# Sheet1.net
KiCad netlist of a schematic drawn in Altium Designer
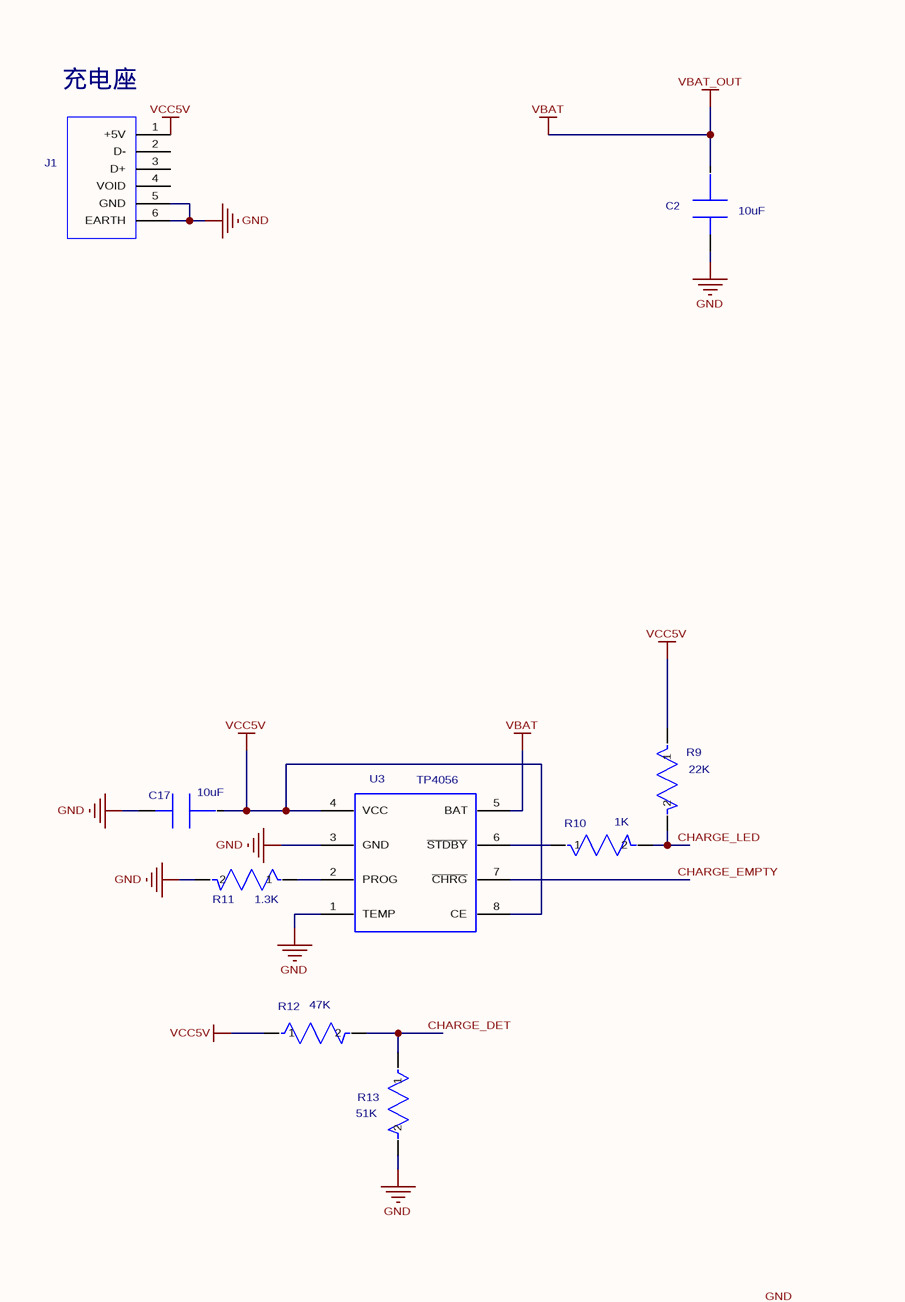
[diagram p0: Sheet1.SchDoc, top column 1 of 4]
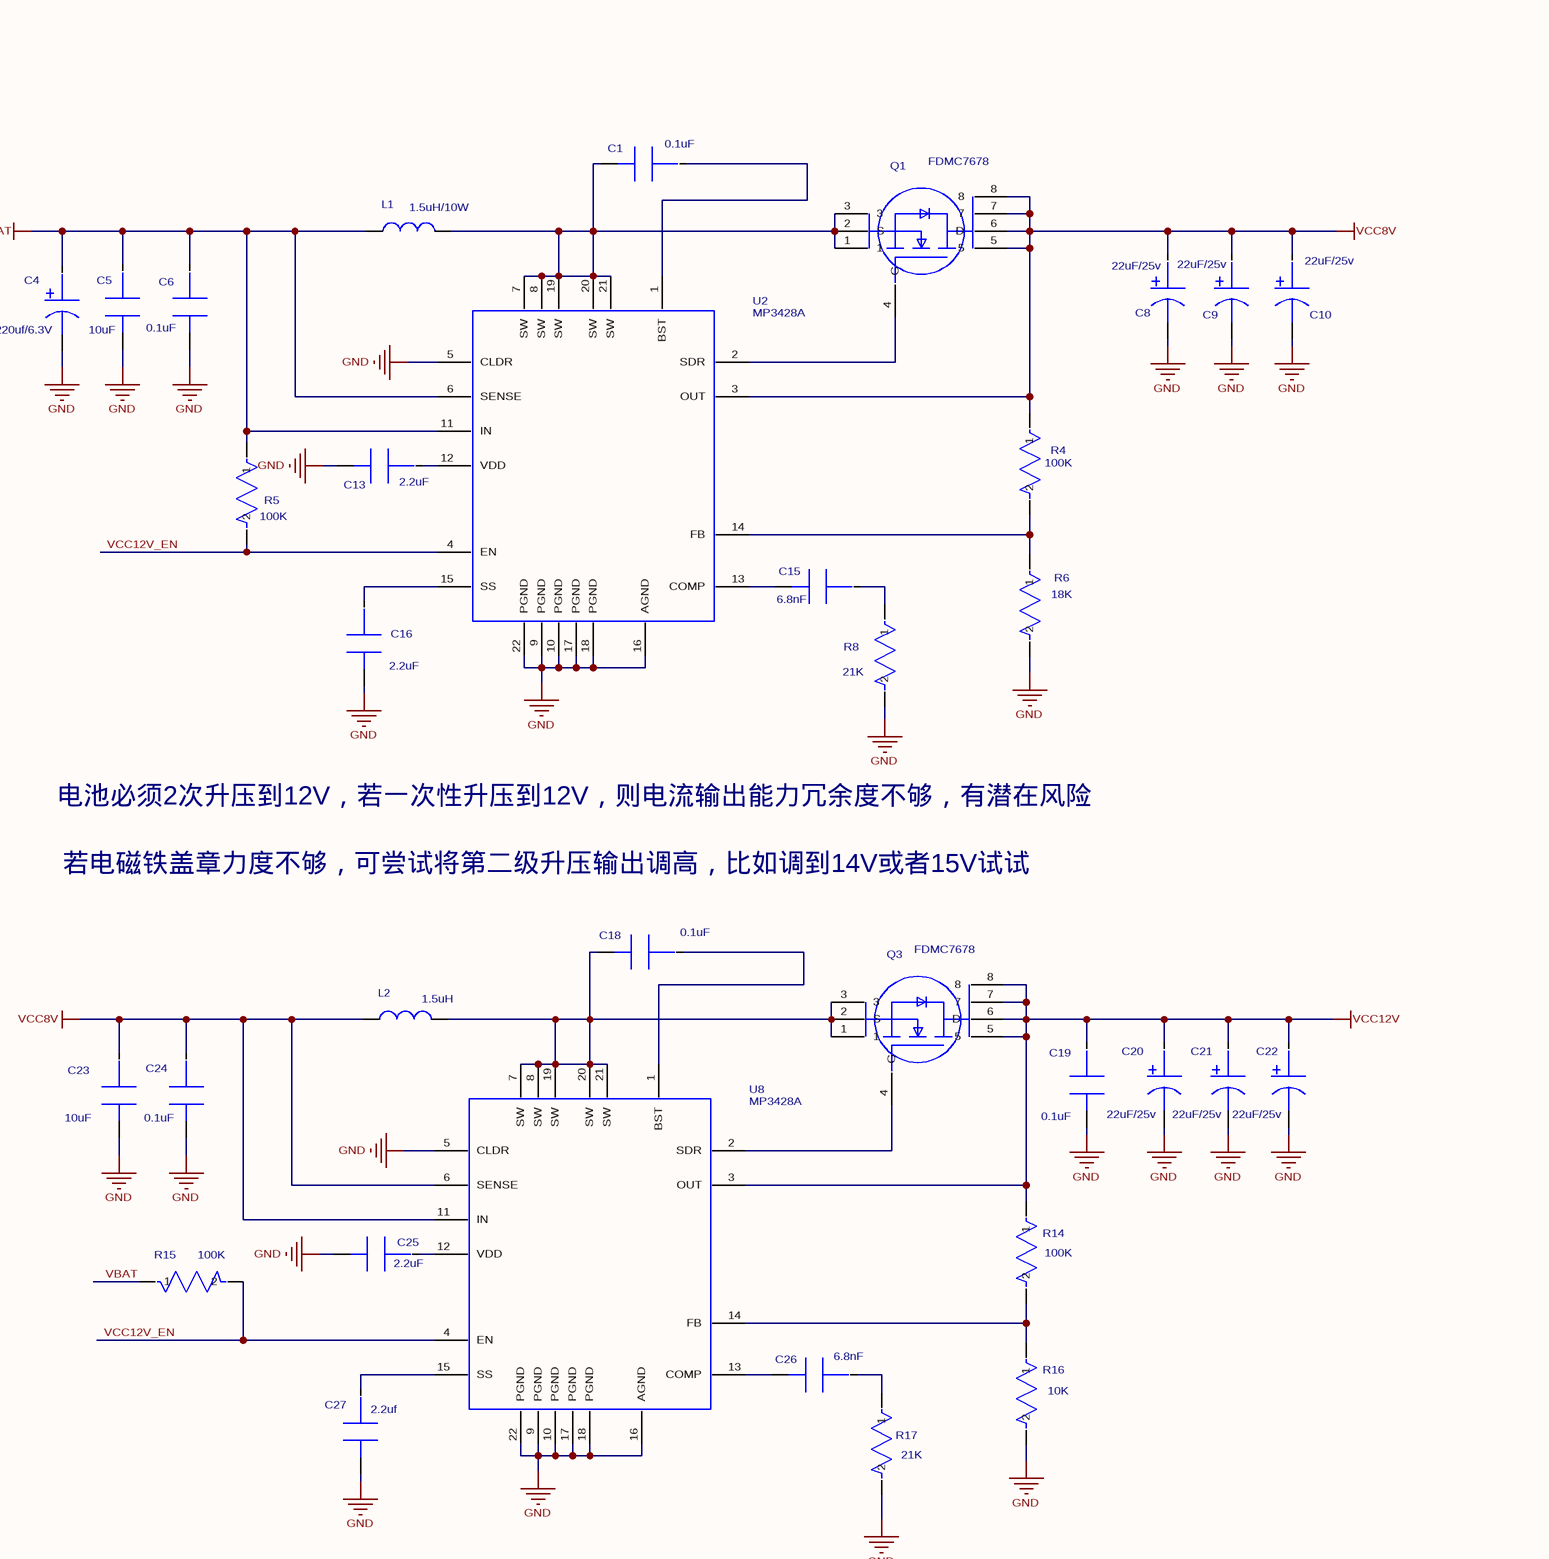
[diagram p1: Sheet1.SchDoc, top column 2 of 4]
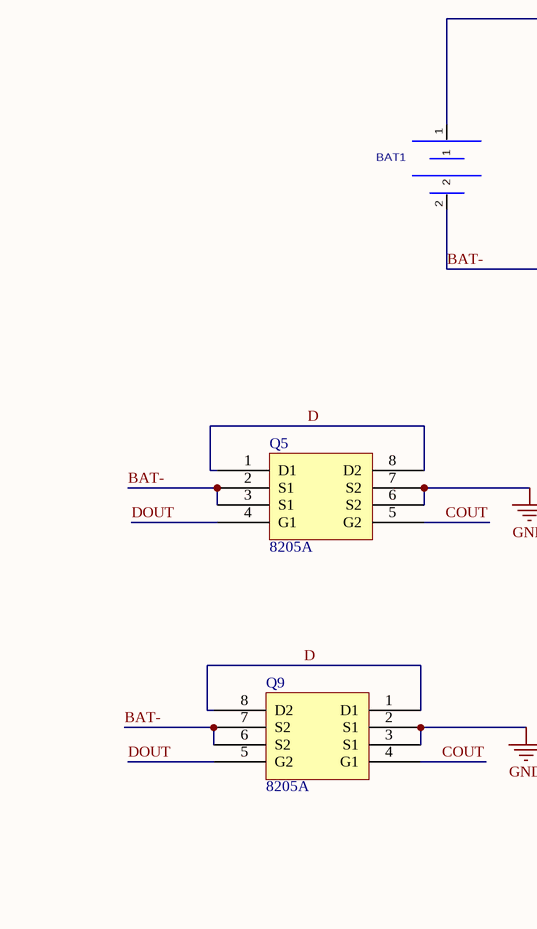
[diagram p2: Sheet1.SchDoc, top column 3 of 4]
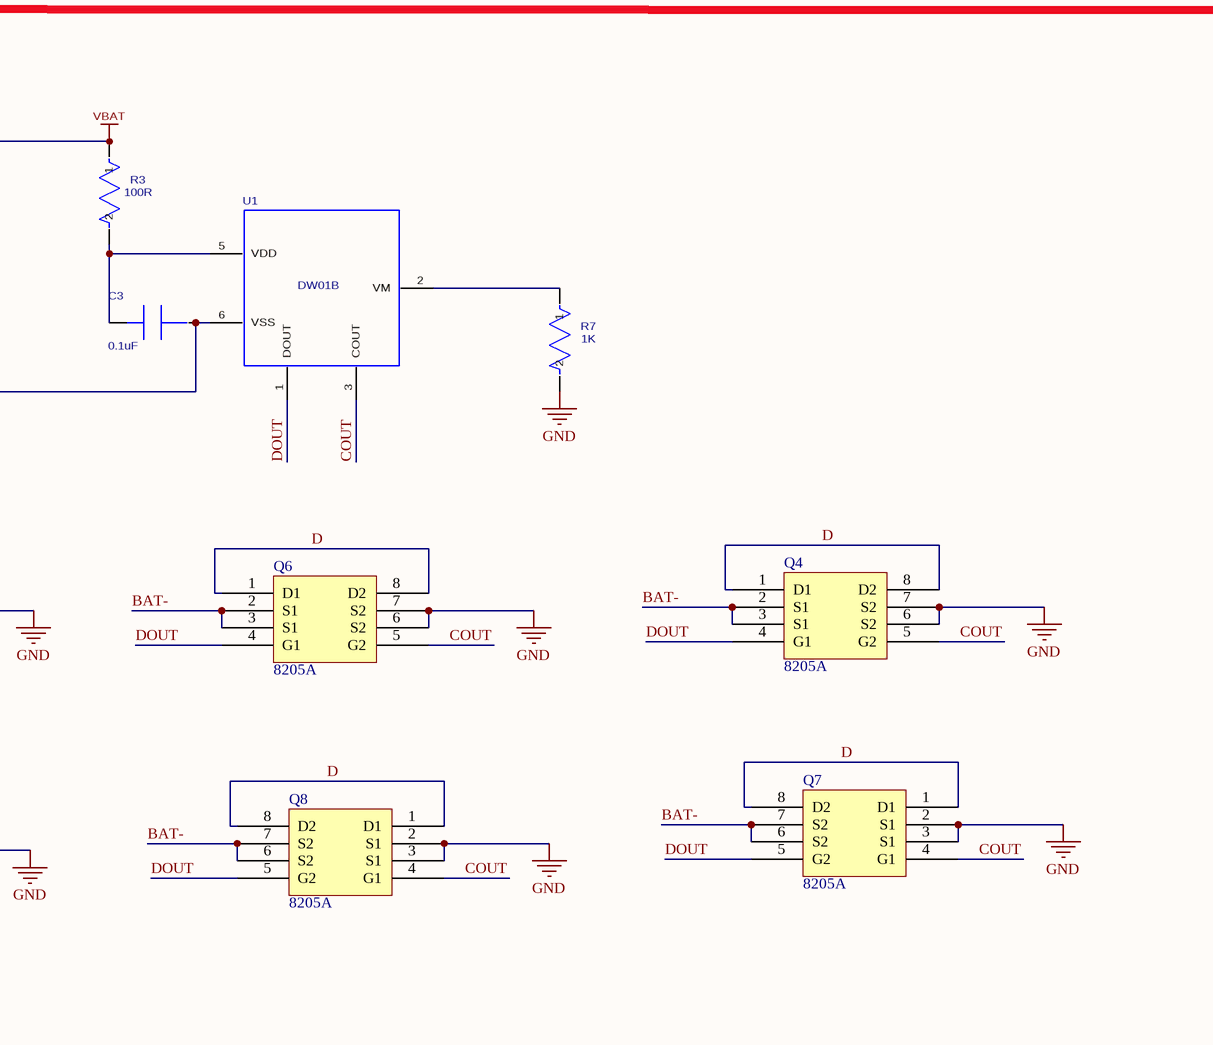
[diagram p3: Sheet1.SchDoc, top column 4 of 4]
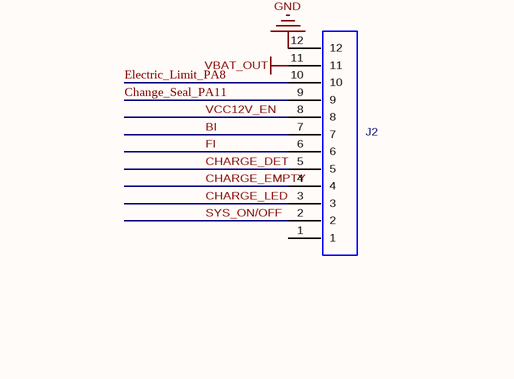
[diagram p4: Sheet1.SchDoc, bottom column 1 of 4]
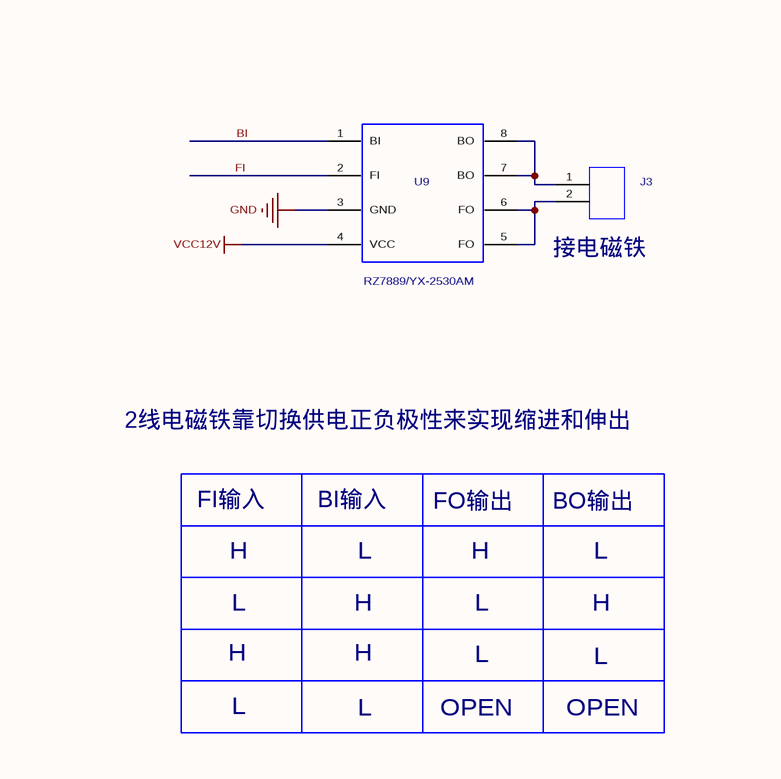
[diagram p5: Sheet1.SchDoc, bottom column 2 of 4]
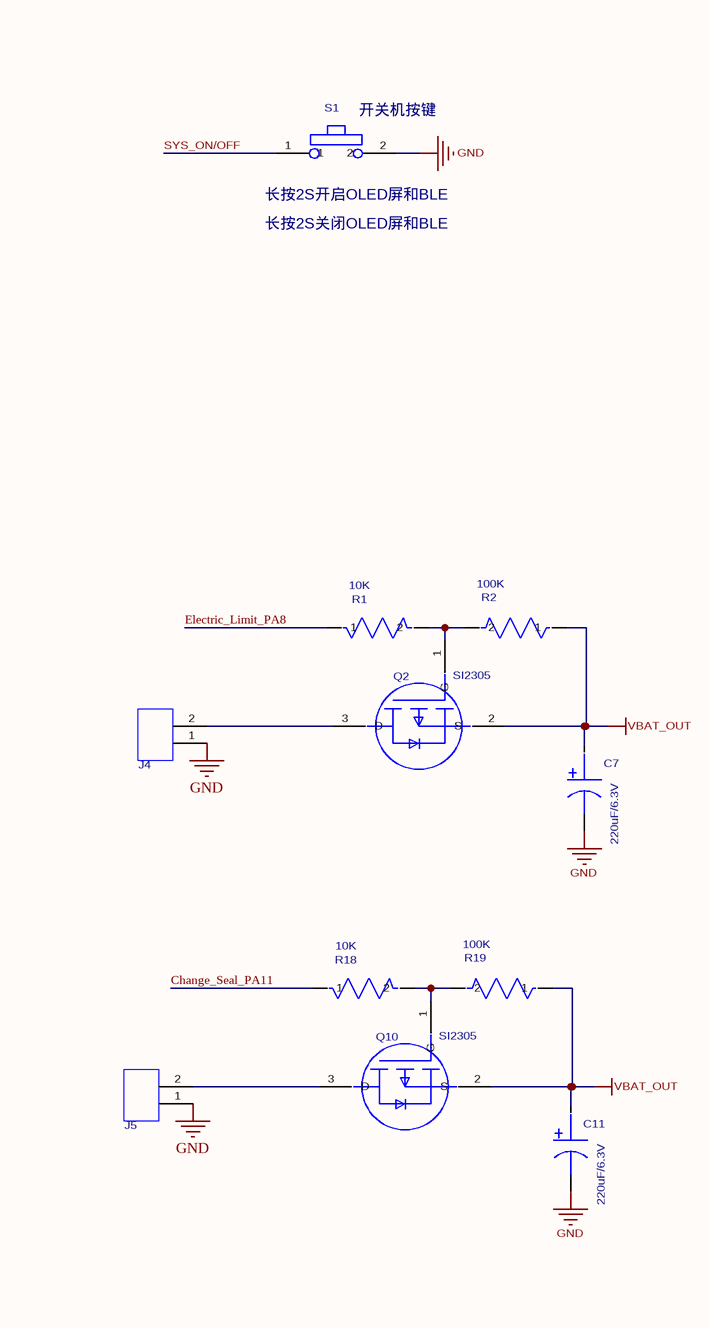
[diagram p6: Sheet1.SchDoc, bottom column 3 of 4]

(export (version "E")
  (design (tool "Eeschema 10.0.6"))
  (components
    (comp (ref "BAT1") (value "BAT1") (footprint "BAT18650_DIP2") (libsource (lib "*") (part "BAT1")))
    (comp (ref "C1") (value "0.1uF") (footprint "C0603") (libsource (lib "") (part "C_1")))
    (comp (ref "C2") (value "10uF") (footprint "C0603") (libsource (lib "") (part "C_1")))
    (comp (ref "C3") (value "0.1uF") (footprint "C0603") (libsource (lib "") (part "C_1")))
    (comp (ref "C4") (value "220uf/6.3V") (footprint "C1210-E") (libsource (lib "*") (part "C")))
    (comp (ref "C5") (value "10uF") (footprint "C0603") (libsource (lib "") (part "C_1")))
    (comp (ref "C6") (value "0.1uF") (footprint "C0603") (libsource (lib "") (part "C_1")))
    (comp (ref "C7") (value "220uF/6.3V") (footprint "C1210-E") (libsource (lib "*") (part "C")))
    (comp (ref "C8") (value "22uF/25v") (footprint "C1210-E") (libsource (lib "*") (part "C")))
    (comp (ref "C9") (value "22uF/25v") (footprint "C1210-E") (libsource (lib "*") (part "C")))
    (comp (ref "C10") (value "22uF/25v") (footprint "C1210-E") (libsource (lib "*") (part "C")))
    (comp (ref "C11") (value "220uF/6.3V") (footprint "C1210-E") (libsource (lib "*") (part "C")))
    (comp (ref "C13") (value "2.2uF") (footprint "C0603") (libsource (lib "") (part "C_1")))
    (comp (ref "C15") (value "6.8nF") (footprint "C0603") (libsource (lib "") (part "C_1")))
    (comp (ref "C16") (value "2.2uF") (footprint "C0603") (libsource (lib "") (part "C_1")))
    (comp (ref "C17") (value "10uF") (footprint "C0603") (libsource (lib "") (part "C_1")))
    (comp (ref "C18") (value "0.1uF") (footprint "C0603") (libsource (lib "") (part "C_1")))
    (comp (ref "C19") (value "0.1uF") (footprint "C0603") (libsource (lib "") (part "C_1")))
    (comp (ref "C20") (value "22uF/25v") (footprint "C1210-E") (libsource (lib "*") (part "C")))
    (comp (ref "C21") (value "22uF/25v") (footprint "C1210-E") (libsource (lib "*") (part "C")))
    (comp (ref "C22") (value "22uF/25v") (footprint "CAP12R5X30") (libsource (lib "*") (part "C")))
    (comp (ref "C23") (value "10uF") (footprint "C0603") (libsource (lib "") (part "C_1")))
    (comp (ref "C24") (value "0.1uF") (footprint "C0603") (libsource (lib "") (part "C_1")))
    (comp (ref "C25") (value "2.2uF") (footprint "C0603") (libsource (lib "") (part "C_1")))
    (comp (ref "C26") (value "6.8nF") (footprint "C0603") (libsource (lib "") (part "C_1")))
    (comp (ref "C27") (value "2.2uf") (footprint "C0603") (libsource (lib "") (part "C_1")))
    (comp (ref "J1") (value "HEADER_6_2") (footprint "MICRO_USB_J") (libsource (lib "*") (part "HEADER_6_2")))
    (comp (ref "J2") (value "CON12") (footprint "CON_12WT") (libsource (lib "*") (part "CON12")))
    (comp (ref "J3") (value "CON2") (footprint "CON1X2-2LOCK") (libsource (lib "*") (part "CON2")))
    (comp (ref "J4") (value "CON2") (footprint "CON1X2-2LOCK") (libsource (lib "*") (part "CON2")))
    (comp (ref "J5") (value "CON2") (footprint "CON1X2-2LOCK") (libsource (lib "*") (part "CON2")))
    (comp (ref "L1") (value "1.5uH/10W") (footprint "L0630") (libsource (lib "*") (part "L")))
    (comp (ref "L2") (value "1.5uH") (footprint "L0630") (libsource (lib "*") (part "L")))
    (comp (ref "Q1") (value "FDMC7678") (footprint "FDMC7678") (libsource (lib "*") (part "FDMC7678")))
    (comp (ref "Q2") (value "SI2305") (footprint "SOT23") (libsource (lib "*") (part "FDN338P")))
    (comp (ref "Q3") (value "FDMC7678") (footprint "FDMC7678") (libsource (lib "*") (part "FDMC7678")))
    (comp (ref "Q4") (value "8205A") (footprint "TSSOP8") (libsource (lib "") (part "8205A-TSSOP8_1")))
    (comp (ref "Q5") (value "8205A") (footprint "TSSOP8") (libsource (lib "") (part "8205A-TSSOP8_1")))
    (comp (ref "Q6") (value "8205A") (footprint "TSSOP8") (libsource (lib "") (part "8205A-TSSOP8_1")))
    (comp (ref "Q7")
      (value "8205A")
      (footprint "TSSOP8")
      (libsource (lib "PCB_Project") (part "8205A-TSSOP8"))
    )
    (comp (ref "Q8")
      (value "8205A")
      (footprint "TSSOP8")
      (libsource (lib "PCB_Project") (part "8205A-TSSOP8"))
    )
    (comp (ref "Q9")
      (value "8205A")
      (footprint "TSSOP8")
      (libsource (lib "PCB_Project") (part "8205A-TSSOP8"))
    )
    (comp (ref "Q10") (value "SI2305") (footprint "SOT23") (libsource (lib "*") (part "FDN338P")))
    (comp (ref "R1") (value "10K") (footprint "R0603") (libsource (lib "*") (part "R")))
    (comp (ref "R2") (value "100K") (footprint "R0603") (libsource (lib "*") (part "R")))
    (comp (ref "R3") (value "100R") (footprint "R0603") (libsource (lib "*") (part "R")))
    (comp (ref "R4") (value "100K") (footprint "R0603") (libsource (lib "*") (part "R")))
    (comp (ref "R5") (value "100K") (footprint "R0603") (libsource (lib "*") (part "R")))
    (comp (ref "R6") (value "18K") (footprint "R0603") (libsource (lib "*") (part "R")))
    (comp (ref "R7") (value "1K") (footprint "R0603") (libsource (lib "*") (part "R")))
    (comp (ref "R8") (value "21K") (footprint "R0603") (libsource (lib "*") (part "R")))
    (comp (ref "R9") (value "22K") (footprint "R0603") (libsource (lib "*") (part "R")))
    (comp (ref "R10") (value "1K") (footprint "R0603") (libsource (lib "*") (part "R")))
    (comp (ref "R11") (value "1.3K") (footprint "R0603") (libsource (lib "*") (part "R")))
    (comp (ref "R12") (value "47K") (footprint "R0603") (libsource (lib "*") (part "R")))
    (comp (ref "R13") (value "51K") (footprint "R0603") (libsource (lib "*") (part "R")))
    (comp (ref "R14") (value "100K") (footprint "R0603") (libsource (lib "*") (part "R")))
    (comp (ref "R15") (value "100K") (footprint "R0603") (libsource (lib "*") (part "R")))
    (comp (ref "R16") (value "10K") (footprint "R0603") (libsource (lib "*") (part "R")))
    (comp (ref "R17") (value "21K") (footprint "R0603") (libsource (lib "*") (part "R")))
    (comp (ref "R18") (value "10K") (footprint "R0603") (libsource (lib "*") (part "R")))
    (comp (ref "R19") (value "100K") (footprint "R0603") (libsource (lib "*") (part "R")))
    (comp (ref "S1") (value "SW_3X6X5") (footprint "SW3X6X3R5") (libsource (lib "*") (part "SW_3X6X5")))
    (comp (ref "U1") (value "DW01B") (footprint "SOT23-6") (libsource (lib "PCB_Project") (part "DW01V")))
    (comp (ref "U2") (value "MP3428A") (footprint "QFN22") (libsource (lib "PCB_Project") (part "MP3428A")))
    (comp (ref "U3") (value "TP4056") (footprint "SOIC8E") (libsource (lib "*") (part "TP4056")))
    (comp (ref "U8") (value "MP3428A") (footprint "QFN22") (libsource (lib "PCB_Project") (part "MP3428A")))
    (comp (ref "U9")
      (value "RZ7889/YX-2530AM")
      (footprint "SO8-5R2-1R27")
      (libsource (lib "*") (part "RZ7889/YX-2530AM"))
    )
  )
  (nets
    (net (code "1") (name "/BAT-") (class "Default")
      (node (ref "BAT1") (pin "2") (pinfunction "2_2") (pintype "passive"))
      (node (ref "C3") (pin "1") (pinfunction "1_1") (pintype "passive"))
      (node (ref "Q4") (pin "2") (pinfunction "S1_2") (pintype "passive"))
      (node (ref "Q4") (pin "3") (pinfunction "S1_3") (pintype "passive"))
      (node (ref "Q5") (pin "2") (pinfunction "S1_2") (pintype "passive"))
      (node (ref "Q5") (pin "3") (pinfunction "S1_3") (pintype "passive"))
      (node (ref "Q6") (pin "2") (pinfunction "S1_2") (pintype "passive"))
      (node (ref "Q6") (pin "3") (pinfunction "S1_3") (pintype "passive"))
      (node (ref "Q7") (pin "6") (pinfunction "S2_6") (pintype "passive"))
      (node (ref "Q7") (pin "7") (pinfunction "S2_7") (pintype "passive"))
      (node (ref "Q8") (pin "6") (pinfunction "S2_6") (pintype "passive"))
      (node (ref "Q8") (pin "7") (pinfunction "S2_7") (pintype "passive"))
      (node (ref "Q9") (pin "6") (pinfunction "S2_6") (pintype "passive"))
      (node (ref "Q9") (pin "7") (pinfunction "S2_7") (pintype "passive"))
      (node (ref "U1") (pin "6") (pinfunction "VSS_6") (pintype "passive"))
    )
    (net (code "2") (name "/BI") (class "Default")
      (node (ref "J2") (pin "7") (pinfunction "7_7") (pintype "passive"))
      (node (ref "U9") (pin "1") (pinfunction "BI_1") (pintype "passive"))
    )
    (net (code "3") (name "/CHARGE_DET") (class "Default")
      (node (ref "J2") (pin "5") (pinfunction "5_5") (pintype "passive"))
      (node (ref "R12") (pin "2") (pinfunction "2_2") (pintype "passive"))
      (node (ref "R13") (pin "1") (pinfunction "1_1") (pintype "passive"))
    )
    (net (code "4") (name "/CHARGE_EMPTY") (class "Default")
      (node (ref "J2") (pin "4") (pinfunction "4_4") (pintype "passive"))
      (node (ref "U3") (pin "7") (pinfunction "CHRG_7") (pintype "passive"))
    )
    (net (code "5") (name "/CHARGE_LED") (class "Default")
      (node (ref "J2") (pin "3") (pinfunction "3_3") (pintype "passive"))
      (node (ref "R10") (pin "2") (pinfunction "2_2") (pintype "passive"))
      (node (ref "R9") (pin "2") (pinfunction "2_2") (pintype "passive"))
    )
    (net (code "6") (name "/COUT") (class "Default")
      (node (ref "Q4") (pin "5") (pinfunction "G2_5") (pintype "passive"))
      (node (ref "Q5") (pin "5") (pinfunction "G2_5") (pintype "passive"))
      (node (ref "Q6") (pin "5") (pinfunction "G2_5") (pintype "passive"))
      (node (ref "Q7") (pin "4") (pinfunction "G1_4") (pintype "passive"))
      (node (ref "Q8") (pin "4") (pinfunction "G1_4") (pintype "passive"))
      (node (ref "Q9") (pin "4") (pinfunction "G1_4") (pintype "passive"))
      (node (ref "U1") (pin "3") (pinfunction "COUT_3") (pintype "passive"))
    )
    (net (code "7") (name "/Change_Seal_PA11") (class "Default")
      (node (ref "J2") (pin "9") (pinfunction "9_9") (pintype "passive"))
      (node (ref "R18") (pin "1") (pinfunction "1_1") (pintype "passive"))
    )
    (net (code "8") (name "/D") (class "Default")
      (node (ref "Q4") (pin "1") (pinfunction "D1_1") (pintype "passive"))
      (node (ref "Q4") (pin "8") (pinfunction "D2_8") (pintype "passive"))
      (node (ref "Q5") (pin "1") (pinfunction "D1_1") (pintype "passive"))
      (node (ref "Q5") (pin "8") (pinfunction "D2_8") (pintype "passive"))
      (node (ref "Q6") (pin "1") (pinfunction "D1_1") (pintype "passive"))
      (node (ref "Q6") (pin "8") (pinfunction "D2_8") (pintype "passive"))
      (node (ref "Q7") (pin "1") (pinfunction "D1_1") (pintype "passive"))
      (node (ref "Q7") (pin "8") (pinfunction "D2_8") (pintype "passive"))
      (node (ref "Q8") (pin "1") (pinfunction "D1_1") (pintype "passive"))
      (node (ref "Q8") (pin "8") (pinfunction "D2_8") (pintype "passive"))
      (node (ref "Q9") (pin "1") (pinfunction "D1_1") (pintype "passive"))
      (node (ref "Q9") (pin "8") (pinfunction "D2_8") (pintype "passive"))
    )
    (net (code "9") (name "/DOUT") (class "Default")
      (node (ref "Q4") (pin "4") (pinfunction "G1_4") (pintype "passive"))
      (node (ref "Q5") (pin "4") (pinfunction "G1_4") (pintype "passive"))
      (node (ref "Q6") (pin "4") (pinfunction "G1_4") (pintype "passive"))
      (node (ref "Q7") (pin "5") (pinfunction "G2_5") (pintype "passive"))
      (node (ref "Q8") (pin "5") (pinfunction "G2_5") (pintype "passive"))
      (node (ref "Q9") (pin "5") (pinfunction "G2_5") (pintype "passive"))
      (node (ref "U1") (pin "1") (pinfunction "DOUT_1") (pintype "passive"))
    )
    (net (code "10") (name "/Electric_Limit_PA8") (class "Default")
      (node (ref "J2") (pin "10") (pinfunction "10_10") (pintype "passive"))
      (node (ref "R1") (pin "1") (pinfunction "1_1") (pintype "passive"))
    )
    (net (code "11") (name "/FI") (class "Default")
      (node (ref "J2") (pin "6") (pinfunction "6_6") (pintype "passive"))
      (node (ref "U9") (pin "2") (pinfunction "FI_2") (pintype "passive"))
    )
    (net (code "12") (name "/SYS_ON{slash}OFF") (class "Default")
      (node (ref "J2") (pin "2") (pinfunction "2_2") (pintype "passive"))
      (node (ref "S1") (pin "1") (pinfunction "1_1") (pintype "passive"))
    )
    (net (code "13") (name "/VCC12V_EN") (class "Default")
      (node (ref "J2") (pin "8") (pinfunction "8_8") (pintype "passive"))
      (node (ref "R15") (pin "2") (pinfunction "2_2") (pintype "passive"))
      (node (ref "R5") (pin "2") (pinfunction "2_2") (pintype "passive"))
      (node (ref "U2") (pin "4") (pinfunction "EN_4") (pintype "passive"))
      (node (ref "U8") (pin "4") (pinfunction "EN_4") (pintype "passive"))
    )
    (net (code "14") (name "GND") (class "Default")
      (node (ref "C10") (pin "2") (pinfunction "2_2") (pintype "passive"))
      (node (ref "C11") (pin "2") (pinfunction "2_2") (pintype "passive"))
      (node (ref "C13") (pin "2") (pinfunction "2_2") (pintype "passive"))
      (node (ref "C16") (pin "2") (pinfunction "2_2") (pintype "passive"))
      (node (ref "C17") (pin "2") (pinfunction "2_2") (pintype "passive"))
      (node (ref "C19") (pin "2") (pinfunction "2_2") (pintype "passive"))
      (node (ref "C2") (pin "2") (pinfunction "2_2") (pintype "passive"))
      (node (ref "C20") (pin "2") (pinfunction "2_2") (pintype "passive"))
      (node (ref "C21") (pin "2") (pinfunction "2_2") (pintype "passive"))
      (node (ref "C22") (pin "2") (pinfunction "2_2") (pintype "passive"))
      (node (ref "C23") (pin "2") (pinfunction "2_2") (pintype "passive"))
      (node (ref "C24") (pin "2") (pinfunction "2_2") (pintype "passive"))
      (node (ref "C25") (pin "2") (pinfunction "2_2") (pintype "passive"))
      (node (ref "C27") (pin "2") (pinfunction "2_2") (pintype "passive"))
      (node (ref "C4") (pin "2") (pinfunction "2_2") (pintype "passive"))
      (node (ref "C5") (pin "2") (pinfunction "2_2") (pintype "passive"))
      (node (ref "C6") (pin "2") (pinfunction "2_2") (pintype "passive"))
      (node (ref "C7") (pin "2") (pinfunction "2_2") (pintype "passive"))
      (node (ref "C8") (pin "2") (pinfunction "2_2") (pintype "passive"))
      (node (ref "C9") (pin "2") (pinfunction "2_2") (pintype "passive"))
      (node (ref "J1") (pin "5") (pinfunction "GND_5") (pintype "passive"))
      (node (ref "J1") (pin "6") (pinfunction "EARTH_6") (pintype "passive"))
      (node (ref "J2") (pin "12") (pinfunction "12_12") (pintype "passive"))
      (node (ref "J4") (pin "1") (pinfunction "1_1") (pintype "passive"))
      (node (ref "J5") (pin "1") (pinfunction "1_1") (pintype "passive"))
      (node (ref "Q4") (pin "6") (pinfunction "S2_6") (pintype "passive"))
      (node (ref "Q4") (pin "7") (pinfunction "S2_7") (pintype "passive"))
      (node (ref "Q5") (pin "6") (pinfunction "S2_6") (pintype "passive"))
      (node (ref "Q5") (pin "7") (pinfunction "S2_7") (pintype "passive"))
      (node (ref "Q6") (pin "6") (pinfunction "S2_6") (pintype "passive"))
      (node (ref "Q6") (pin "7") (pinfunction "S2_7") (pintype "passive"))
      (node (ref "Q7") (pin "2") (pinfunction "S1_2") (pintype "passive"))
      (node (ref "Q7") (pin "3") (pinfunction "S1_3") (pintype "passive"))
      (node (ref "Q8") (pin "2") (pinfunction "S1_2") (pintype "passive"))
      (node (ref "Q8") (pin "3") (pinfunction "S1_3") (pintype "passive"))
      (node (ref "Q9") (pin "2") (pinfunction "S1_2") (pintype "passive"))
      (node (ref "Q9") (pin "3") (pinfunction "S1_3") (pintype "passive"))
      (node (ref "R11") (pin "2") (pinfunction "2_2") (pintype "passive"))
      (node (ref "R13") (pin "2") (pinfunction "2_2") (pintype "passive"))
      (node (ref "R16") (pin "2") (pinfunction "2_2") (pintype "passive"))
      (node (ref "R17") (pin "2") (pinfunction "2_2") (pintype "passive"))
      (node (ref "R6") (pin "2") (pinfunction "2_2") (pintype "passive"))
      (node (ref "R7") (pin "2") (pinfunction "2_2") (pintype "passive"))
      (node (ref "R8") (pin "2") (pinfunction "2_2") (pintype "passive"))
      (node (ref "S1") (pin "2") (pinfunction "2_2") (pintype "passive"))
      (node (ref "U2") (pin "10") (pinfunction "PGND_10") (pintype "passive"))
      (node (ref "U2") (pin "16") (pinfunction "AGND_16") (pintype "passive"))
      (node (ref "U2") (pin "17") (pinfunction "PGND_17") (pintype "passive"))
      (node (ref "U2") (pin "18") (pinfunction "PGND_18") (pintype "passive"))
      (node (ref "U2") (pin "22") (pinfunction "PGND_22") (pintype "passive"))
      (node (ref "U2") (pin "5") (pinfunction "CLDR_5") (pintype "passive"))
      (node (ref "U2") (pin "9") (pinfunction "PGND_9") (pintype "passive"))
      (node (ref "U3") (pin "1") (pinfunction "TEMP_1") (pintype "passive"))
      (node (ref "U3") (pin "3") (pinfunction "GND_3") (pintype "passive"))
      (node (ref "U8") (pin "10") (pinfunction "PGND_10") (pintype "passive"))
      (node (ref "U8") (pin "16") (pinfunction "AGND_16") (pintype "passive"))
      (node (ref "U8") (pin "17") (pinfunction "PGND_17") (pintype "passive"))
      (node (ref "U8") (pin "18") (pinfunction "PGND_18") (pintype "passive"))
      (node (ref "U8") (pin "22") (pinfunction "PGND_22") (pintype "passive"))
      (node (ref "U8") (pin "5") (pinfunction "CLDR_5") (pintype "passive"))
      (node (ref "U8") (pin "9") (pinfunction "PGND_9") (pintype "passive"))
      (node (ref "U9") (pin "3") (pinfunction "GND_3") (pintype "passive"))
    )
    (net (code "15") (name "Net-(C15-Pad1)") (class "Default")
      (node (ref "C15") (pin "1") (pinfunction "1_1") (pintype "passive"))
      (node (ref "R8") (pin "1") (pinfunction "1_1") (pintype "passive"))
    )
    (net (code "16") (name "Net-(C26-Pad1)") (class "Default")
      (node (ref "C26") (pin "1") (pinfunction "1_1") (pintype "passive"))
      (node (ref "R17") (pin "1") (pinfunction "1_1") (pintype "passive"))
    )
    (net (code "17") (name "Net-(J3-Pad1)") (class "Default")
      (node (ref "J3") (pin "1") (pinfunction "1_1") (pintype "passive"))
      (node (ref "U9") (pin "7") (pinfunction "BO_7") (pintype "passive"))
      (node (ref "U9") (pin "8") (pinfunction "BO_8") (pintype "passive"))
    )
    (net (code "18") (name "Net-(J3-Pad2)") (class "Default")
      (node (ref "J3") (pin "2") (pinfunction "2_2") (pintype "passive"))
      (node (ref "U9") (pin "5") (pinfunction "FO_5") (pintype "passive"))
      (node (ref "U9") (pin "6") (pinfunction "FO_6") (pintype "passive"))
    )
    (net (code "19") (name "Net-(Q1-G)") (class "Default")
      (node (ref "Q1") (pin "4") (pinfunction "G_4") (pintype "passive"))
      (node (ref "U2") (pin "2") (pinfunction "SDR_2") (pintype "passive"))
    )
    (net (code "20") (name "Net-(Q1-S)") (class "Default")
      (node (ref "C1") (pin "2") (pinfunction "2_2") (pintype "passive"))
      (node (ref "L1") (pin "2") (pinfunction "2_2") (pintype "passive"))
      (node (ref "Q1") (pin "1") (pinfunction "1_1") (pintype "passive"))
      (node (ref "Q1") (pin "2") (pinfunction "S_2") (pintype "passive"))
      (node (ref "Q1") (pin "3") (pinfunction "3_3") (pintype "passive"))
      (node (ref "U2") (pin "19") (pinfunction "SW_19") (pintype "passive"))
      (node (ref "U2") (pin "20") (pinfunction "SW_20") (pintype "passive"))
      (node (ref "U2") (pin "21") (pinfunction "SW_21") (pintype "passive"))
      (node (ref "U2") (pin "7") (pinfunction "SW_7") (pintype "passive"))
      (node (ref "U2") (pin "8") (pinfunction "SW_8") (pintype "passive"))
    )
    (net (code "21") (name "Net-(Q2-D)") (class "Default")
      (node (ref "J4") (pin "2") (pinfunction "2_2") (pintype "passive"))
      (node (ref "Q2") (pin "3") (pinfunction "D_3") (pintype "passive"))
    )
    (net (code "22") (name "Net-(Q2-G)") (class "Default")
      (node (ref "Q2") (pin "1") (pinfunction "G_1") (pintype "passive"))
      (node (ref "R1") (pin "2") (pinfunction "2_2") (pintype "passive"))
      (node (ref "R2") (pin "2") (pinfunction "2_2") (pintype "passive"))
    )
    (net (code "23") (name "Net-(Q3-G)") (class "Default")
      (node (ref "Q3") (pin "4") (pinfunction "G_4") (pintype "passive"))
      (node (ref "U8") (pin "2") (pinfunction "SDR_2") (pintype "passive"))
    )
    (net (code "24") (name "Net-(Q3-S)") (class "Default")
      (node (ref "C18") (pin "2") (pinfunction "2_2") (pintype "passive"))
      (node (ref "L2") (pin "2") (pinfunction "2_2") (pintype "passive"))
      (node (ref "Q3") (pin "1") (pinfunction "1_1") (pintype "passive"))
      (node (ref "Q3") (pin "2") (pinfunction "S_2") (pintype "passive"))
      (node (ref "Q3") (pin "3") (pinfunction "3_3") (pintype "passive"))
      (node (ref "U8") (pin "19") (pinfunction "SW_19") (pintype "passive"))
      (node (ref "U8") (pin "20") (pinfunction "SW_20") (pintype "passive"))
      (node (ref "U8") (pin "21") (pinfunction "SW_21") (pintype "passive"))
      (node (ref "U8") (pin "7") (pinfunction "SW_7") (pintype "passive"))
      (node (ref "U8") (pin "8") (pinfunction "SW_8") (pintype "passive"))
    )
    (net (code "25") (name "Net-(Q10-D)") (class "Default")
      (node (ref "J5") (pin "2") (pinfunction "2_2") (pintype "passive"))
      (node (ref "Q10") (pin "3") (pinfunction "D_3") (pintype "passive"))
    )
    (net (code "26") (name "Net-(Q10-G)") (class "Default")
      (node (ref "Q10") (pin "1") (pinfunction "G_1") (pintype "passive"))
      (node (ref "R18") (pin "2") (pinfunction "2_2") (pintype "passive"))
      (node (ref "R19") (pin "2") (pinfunction "2_2") (pintype "passive"))
    )
    (net (code "27") (name "Net-(U1-VDD)") (class "Default")
      (node (ref "C3") (pin "2") (pinfunction "2_2") (pintype "passive"))
      (node (ref "R3") (pin "2") (pinfunction "2_2") (pintype "passive"))
      (node (ref "U1") (pin "5") (pinfunction "VDD_5") (pintype "passive"))
    )
    (net (code "28") (name "Net-(U1-VM)") (class "Default")
      (node (ref "R7") (pin "1") (pinfunction "1_1") (pintype "passive"))
      (node (ref "U1") (pin "2") (pinfunction "VM_2") (pintype "passive"))
    )
    (net (code "29") (name "Net-(U2-BST)") (class "Default")
      (node (ref "C1") (pin "1") (pinfunction "1_1") (pintype "passive"))
      (node (ref "U2") (pin "1") (pinfunction "BST_1") (pintype "passive"))
    )
    (net (code "30") (name "Net-(U2-COMP)") (class "Default")
      (node (ref "C15") (pin "2") (pinfunction "2_2") (pintype "passive"))
      (node (ref "U2") (pin "13") (pinfunction "COMP_13") (pintype "passive"))
    )
    (net (code "31") (name "Net-(U2-FB)") (class "Default")
      (node (ref "R4") (pin "2") (pinfunction "2_2") (pintype "passive"))
      (node (ref "R6") (pin "1") (pinfunction "1_1") (pintype "passive"))
      (node (ref "U2") (pin "14") (pinfunction "FB_14") (pintype "passive"))
    )
    (net (code "32") (name "Net-(U2-SS)") (class "Default")
      (node (ref "C16") (pin "1") (pinfunction "1_1") (pintype "passive"))
      (node (ref "U2") (pin "15") (pinfunction "SS_15") (pintype "passive"))
    )
    (net (code "33") (name "Net-(U2-VDD)") (class "Default")
      (node (ref "C13") (pin "1") (pinfunction "1_1") (pintype "passive"))
      (node (ref "U2") (pin "12") (pinfunction "VDD_12") (pintype "passive"))
    )
    (net (code "34") (name "Net-(U3-PROG)") (class "Default")
      (node (ref "R11") (pin "1") (pinfunction "1_1") (pintype "passive"))
      (node (ref "U3") (pin "2") (pinfunction "PROG_2") (pintype "passive"))
    )
    (net (code "35") (name "Net-(U3-STDBY)") (class "Default")
      (node (ref "R10") (pin "1") (pinfunction "1_1") (pintype "passive"))
      (node (ref "U3") (pin "6") (pinfunction "STDBY_6") (pintype "passive"))
    )
    (net (code "36") (name "Net-(U8-BST)") (class "Default")
      (node (ref "C18") (pin "1") (pinfunction "1_1") (pintype "passive"))
      (node (ref "U8") (pin "1") (pinfunction "BST_1") (pintype "passive"))
    )
    (net (code "37") (name "Net-(U8-COMP)") (class "Default")
      (node (ref "C26") (pin "2") (pinfunction "2_2") (pintype "passive"))
      (node (ref "U8") (pin "13") (pinfunction "COMP_13") (pintype "passive"))
    )
    (net (code "38") (name "Net-(U8-FB)") (class "Default")
      (node (ref "R14") (pin "2") (pinfunction "2_2") (pintype "passive"))
      (node (ref "R16") (pin "1") (pinfunction "1_1") (pintype "passive"))
      (node (ref "U8") (pin "14") (pinfunction "FB_14") (pintype "passive"))
    )
    (net (code "39") (name "Net-(U8-SS)") (class "Default")
      (node (ref "C27") (pin "1") (pinfunction "1_1") (pintype "passive"))
      (node (ref "U8") (pin "15") (pinfunction "SS_15") (pintype "passive"))
    )
    (net (code "40") (name "Net-(U8-VDD)") (class "Default")
      (node (ref "C25") (pin "1") (pinfunction "1_1") (pintype "passive"))
      (node (ref "U8") (pin "12") (pinfunction "VDD_12") (pintype "passive"))
    )
    (net (code "41") (name "VBAT") (class "Default")
      (node (ref "BAT1") (pin "1") (pinfunction "1_1") (pintype "passive"))
      (node (ref "C11") (pin "1") (pinfunction "1_1") (pintype "passive"))
      (node (ref "C2") (pin "1") (pinfunction "1_1") (pintype "passive"))
      (node (ref "C4") (pin "1") (pinfunction "1_1") (pintype "passive"))
      (node (ref "C5") (pin "1") (pinfunction "1_1") (pintype "passive"))
      (node (ref "C6") (pin "1") (pinfunction "1_1") (pintype "passive"))
      (node (ref "C7") (pin "1") (pinfunction "1_1") (pintype "passive"))
      (node (ref "J2") (pin "11") (pinfunction "11_11") (pintype "passive"))
      (node (ref "L1") (pin "1") (pinfunction "1_1") (pintype "passive"))
      (node (ref "Q10") (pin "2") (pinfunction "S_2") (pintype "passive"))
      (node (ref "Q2") (pin "2") (pinfunction "S_2") (pintype "passive"))
      (node (ref "R15") (pin "1") (pinfunction "1_1") (pintype "passive"))
      (node (ref "R19") (pin "1") (pinfunction "1_1") (pintype "passive"))
      (node (ref "R2") (pin "1") (pinfunction "1_1") (pintype "passive"))
      (node (ref "R3") (pin "1") (pinfunction "1_1") (pintype "passive"))
      (node (ref "R5") (pin "1") (pinfunction "1_1") (pintype "passive"))
      (node (ref "U2") (pin "11") (pinfunction "IN_11") (pintype "passive"))
      (node (ref "U2") (pin "6") (pinfunction "SENSE_6") (pintype "passive"))
      (node (ref "U3") (pin "5") (pinfunction "BAT_5") (pintype "passive"))
    )
    (net (code "42") (name "VCC5V") (class "Default")
      (node (ref "C17") (pin "1") (pinfunction "1_1") (pintype "passive"))
      (node (ref "J1") (pin "1") (pinfunction "+5V_1") (pintype "passive"))
      (node (ref "R12") (pin "1") (pinfunction "1_1") (pintype "passive"))
      (node (ref "R9") (pin "1") (pinfunction "1_1") (pintype "passive"))
      (node (ref "U3") (pin "4") (pinfunction "VCC_4") (pintype "passive"))
      (node (ref "U3") (pin "8") (pinfunction "CE_8") (pintype "passive"))
    )
    (net (code "43") (name "VCC8V") (class "Default")
      (node (ref "C10") (pin "1") (pinfunction "1_1") (pintype "passive"))
      (node (ref "C23") (pin "1") (pinfunction "1_1") (pintype "passive"))
      (node (ref "C24") (pin "1") (pinfunction "1_1") (pintype "passive"))
      (node (ref "C8") (pin "1") (pinfunction "1_1") (pintype "passive"))
      (node (ref "C9") (pin "1") (pinfunction "1_1") (pintype "passive"))
      (node (ref "L2") (pin "1") (pinfunction "1_1") (pintype "passive"))
      (node (ref "Q1") (pin "5") (pinfunction "5_5") (pintype "passive"))
      (node (ref "Q1") (pin "6") (pinfunction "D_6") (pintype "passive"))
      (node (ref "Q1") (pin "7") (pinfunction "7_7") (pintype "passive"))
      (node (ref "Q1") (pin "8") (pinfunction "8_8") (pintype "passive"))
      (node (ref "R4") (pin "1") (pinfunction "1_1") (pintype "passive"))
      (node (ref "U2") (pin "3") (pinfunction "OUT_3") (pintype "passive"))
      (node (ref "U8") (pin "11") (pinfunction "IN_11") (pintype "passive"))
      (node (ref "U8") (pin "6") (pinfunction "SENSE_6") (pintype "passive"))
    )
    (net (code "44") (name "VCC12V") (class "Default")
      (node (ref "C19") (pin "1") (pinfunction "1_1") (pintype "passive"))
      (node (ref "C20") (pin "1") (pinfunction "1_1") (pintype "passive"))
      (node (ref "C21") (pin "1") (pinfunction "1_1") (pintype "passive"))
      (node (ref "C22") (pin "1") (pinfunction "1_1") (pintype "passive"))
      (node (ref "Q3") (pin "5") (pinfunction "5_5") (pintype "passive"))
      (node (ref "Q3") (pin "6") (pinfunction "D_6") (pintype "passive"))
      (node (ref "Q3") (pin "7") (pinfunction "7_7") (pintype "passive"))
      (node (ref "Q3") (pin "8") (pinfunction "8_8") (pintype "passive"))
      (node (ref "R14") (pin "1") (pinfunction "1_1") (pintype "passive"))
      (node (ref "U8") (pin "3") (pinfunction "OUT_3") (pintype "passive"))
      (node (ref "U9") (pin "4") (pinfunction "VCC_4") (pintype "passive"))
    )
    (net (code "45") (name "unconnected-(J1-D+-Pad3)") (class "Default")
      (node (ref "J1") (pin "3") (pinfunction "D+_3") (pintype "passive"))
    )
    (net (code "46") (name "unconnected-(J1-D--Pad2)") (class "Default")
      (node (ref "J1") (pin "2") (pinfunction "D-_2") (pintype "passive"))
    )
    (net (code "47") (name "unconnected-(J1-VOID-Pad4)") (class "Default")
      (node (ref "J1") (pin "4") (pinfunction "VOID_4") (pintype "passive"))
    )
    (net (code "48") (name "unconnected-(J2-Pad1)") (class "Default")
      (node (ref "J2") (pin "1") (pinfunction "1_1") (pintype "passive"))
    )
  )
)
